# Boost-NEW.net
KiCad netlist of a schematic drawn in EAGLE
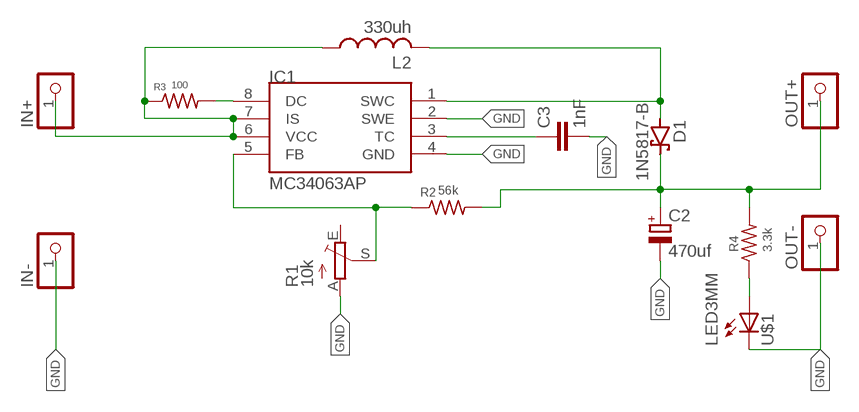
[diagram p0: schematic, sheet 1]

(export (version "E")
  (design (tool "Eeschema 10.0.6"))
  (components
    (comp (ref "C2")
      (value "470uf")
      (footprint "eagle-import:E3,5-8")
      (fields (field (name "SPICEPREFIX") "C"))
      (libsource (lib "eagle-import") (part "CAP_POL"))
    )
    (comp (ref "C3")
      (value "1nF")
      (footprint "eagle-import:C025-025X050")
      (fields (field (name "SPICEPREFIX") "C"))
      (libsource (lib "eagle-import") (part "CAPACITOR"))
    )
    (comp (ref "D1")
      (value "1N5817-B")
      (footprint "eagle-import:DO41-7.6")
      (fields (field (name "SPICEPREFIX") "D"))
      (libsource (lib "eagle-import") (part "1N5817-B"))
    )
    (comp (ref "IC1")
      (value "MC34063AP")
      (footprint "eagle-import:DIL08")
      (fields (field (name "SPICEPREFIX") "X"))
      (libsource (lib "eagle-import") (part "MC34063AP"))
    )
    (comp (ref "IN+")
      (value "PINHD-1X1")
      (footprint "eagle-import:1X01")
      (fields (field (name "SPICEPREFIX") "X"))
      (libsource (lib "eagle-import") (part "PINHD-1X1"))
    )
    (comp (ref "IN-")
      (value "PINHD-1X1")
      (footprint "eagle-import:1X01")
      (fields (field (name "SPICEPREFIX") "X"))
      (libsource (lib "eagle-import") (part "PINHD-1X1"))
    )
    (comp (ref "L2")
      (value "330uh")
      (footprint "eagle-import:POWER-CHOKE_WE-TPC")
      (libsource (lib "eagle-import") (part "L-USWE-TPC"))
    )
    (comp (ref "OUT+")
      (value "PINHD-1X1")
      (footprint "eagle-import:1X01")
      (fields (field (name "SPICEPREFIX") "X"))
      (libsource (lib "eagle-import") (part "PINHD-1X1"))
    )
    (comp (ref "OUT-")
      (value "PINHD-1X1")
      (footprint "eagle-import:1X01")
      (fields (field (name "SPICEPREFIX") "X"))
      (libsource (lib "eagle-import") (part "PINHD-1X1"))
    )
    (comp (ref "R1")
      (value "10k")
      (footprint "eagle-import:CA6V")
      (fields (field (name "SPICEPREFIX") "J"))
      (libsource (lib "eagle-import") (part "TRIM_EU-CA6V"))
    )
    (comp (ref "R2")
      (value "56k")
      (footprint "eagle-import:0204_7")
      (fields (field (name "SPICEPREFIX") "R"))
      (libsource (lib "eagle-import") (part "RES-7"))
    )
    (comp (ref "R3")
      (value "100")
      (footprint "eagle-import:0204_7")
      (fields (field (name "SPICEPREFIX") "R"))
      (libsource (lib "eagle-import") (part "RES-7"))
    )
    (comp (ref "R4")
      (value "3.3k")
      (footprint "eagle-import:0204_7")
      (fields (field (name "SPICEPREFIX") "R"))
      (libsource (lib "eagle-import") (part "RES-7"))
    )
    (comp (ref "U$1")
      (value "LED3MM")
      (footprint "eagle-import:LED3MM")
      (fields (field (name "SPICEPREFIX") "B"))
      (libsource (lib "eagle-import") (part "LED3MM"))
    )
  )
  (nets
    (net (code "1") (name "GND") (class "Default")
      (node (ref "C2") (pin "-") (pinfunction "-_-") (pintype "passive"))
      (node (ref "C3") (pin "2") (pinfunction "2_2") (pintype "passive"))
      (node (ref "IC1") (pin "2") (pinfunction "SWE_2") (pintype "passive"))
      (node (ref "IC1") (pin "4") (pinfunction "GND_4") (pintype "passive"))
      (node (ref "IN-") (pin "1") (pinfunction "1_1") (pintype "passive"))
      (node (ref "OUT-") (pin "1") (pinfunction "1_1") (pintype "passive"))
      (node (ref "R1") (pin "A") (pinfunction "A_A") (pintype "passive"))
      (node (ref "U$1") (pin "K") (pinfunction "C_K") (pintype "passive"))
    )
    (net (code "2") (name "Net-(C2-Pad+)") (class "Default")
      (node (ref "C2") (pin "+") (pinfunction "+_+") (pintype "passive"))
      (node (ref "D1") (pin "C") (pinfunction "C_C") (pintype "passive"))
      (node (ref "OUT+") (pin "1") (pinfunction "1_1") (pintype "passive"))
      (node (ref "R2") (pin "2") (pinfunction "2_2") (pintype "passive"))
      (node (ref "R4") (pin "2") (pinfunction "2_2") (pintype "passive"))
    )
    (net (code "3") (name "Net-(IC1-DC)") (class "Default")
      (node (ref "IC1") (pin "8") (pinfunction "DC_8") (pintype "passive"))
      (node (ref "R3") (pin "2") (pinfunction "2_2") (pintype "passive"))
    )
    (net (code "4") (name "Net-(IC1-FB)") (class "Default")
      (node (ref "IC1") (pin "5") (pinfunction "FB_5") (pintype "passive"))
      (node (ref "R1") (pin "S") (pinfunction "S_S") (pintype "passive"))
      (node (ref "R2") (pin "1") (pinfunction "1_1") (pintype "passive"))
    )
    (net (code "5") (name "Net-(IC1-IS)") (class "Default")
      (node (ref "IC1") (pin "6") (pinfunction "VCC_6") (pintype "passive"))
      (node (ref "IC1") (pin "7") (pinfunction "IS_7") (pintype "passive"))
      (node (ref "IN+") (pin "1") (pinfunction "1_1") (pintype "passive"))
      (node (ref "L2") (pin "1") (pinfunction "1_1") (pintype "passive"))
      (node (ref "R3") (pin "1") (pinfunction "1_1") (pintype "passive"))
    )
    (net (code "6") (name "Net-(IC1-SWC)") (class "Default")
      (node (ref "D1") (pin "A") (pinfunction "A_A") (pintype "passive"))
      (node (ref "IC1") (pin "1") (pinfunction "SWC_1") (pintype "passive"))
      (node (ref "L2") (pin "2") (pinfunction "2_2") (pintype "passive"))
    )
    (net (code "7") (name "Net-(IC1-TC)") (class "Default")
      (node (ref "C3") (pin "1") (pinfunction "1_1") (pintype "passive"))
      (node (ref "IC1") (pin "3") (pinfunction "TC_3") (pintype "passive"))
    )
    (net (code "8") (name "Net-(R4-Pad1)") (class "Default")
      (node (ref "R4") (pin "1") (pinfunction "1_1") (pintype "passive"))
      (node (ref "U$1") (pin "A") (pinfunction "A_A") (pintype "passive"))
    )
    (net (code "9") (name "unconnected-(R1-PadE)") (class "Default")
      (node (ref "R1") (pin "E") (pinfunction "E_E") (pintype "passive"))
    )
  )
)
